# Schematic.net
KiCad netlist of a schematic drawn in EAGLE
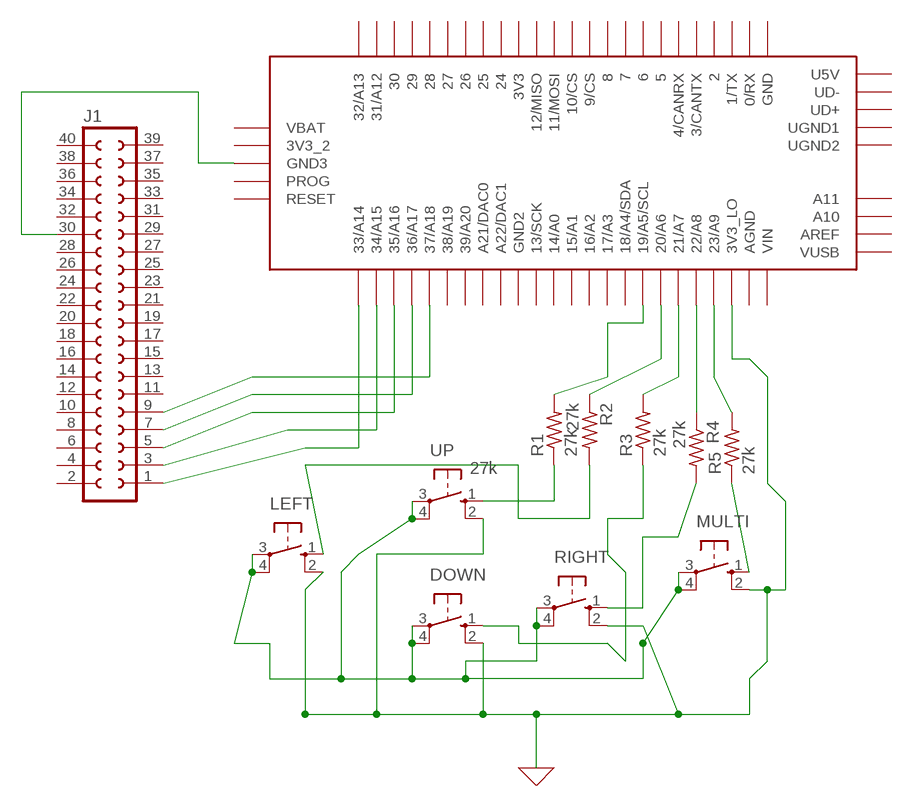
[diagram p0: schematic, sheet 1]

(export (version "E")
  (design (tool "Eeschema 10.0.6"))
  (components
    (comp (ref "DOWN")
      (value "27k")
      (footprint "eagle-import:B3F-10XX")
      (fields (field (name "MPN") "B3F-1000"))
      (libsource (lib "eagle-import") (part "10-XX"))
    )
    (comp (ref "J1")
      (value "SOCKET-40V")
      (footprint "eagle-import:S40V")
      (libsource (lib "eagle-import") (part "SOCKET-40V"))
    )
    (comp (ref "LEFT")
      (value "27k")
      (footprint "eagle-import:B3F-10XX")
      (fields (field (name "MPN") "B3F-1000"))
      (libsource (lib "eagle-import") (part "10-XX"))
    )
    (comp (ref "MULTI")
      (value "27k")
      (footprint "eagle-import:B3F-10XX")
      (fields (field (name "MPN") "B3F-1000"))
      (libsource (lib "eagle-import") (part "10-XX"))
    )
    (comp (ref "R1")
      (value "27k")
      (footprint "eagle-import:0204V")
      (libsource (lib "eagle-import") (part "R-US_0204/2V"))
    )
    (comp (ref "R2")
      (value "27k")
      (footprint "eagle-import:0204V")
      (libsource (lib "eagle-import") (part "R-US_0204/2V"))
    )
    (comp (ref "R3")
      (value "27k")
      (footprint "eagle-import:0204V")
      (libsource (lib "eagle-import") (part "R-US_0204/2V"))
    )
    (comp (ref "R4")
      (value "27k")
      (footprint "eagle-import:0204V")
      (libsource (lib "eagle-import") (part "R-US_0204/2V"))
    )
    (comp (ref "R5")
      (value "27k")
      (footprint "eagle-import:0204V")
      (libsource (lib "eagle-import") (part "R-US_0204/2V"))
    )
    (comp (ref "RIGHT")
      (value "27k")
      (footprint "eagle-import:B3F-10XX")
      (fields (field (name "MPN") "B3F-1000"))
      (libsource (lib "eagle-import") (part "10-XX"))
    )
    (comp (ref "U$2")
      (value "TEENSY_3.5/3.6")
      (footprint "eagle-import:TEENSY_3.5_3.6")
      (libsource (lib "eagle-import") (part "TEENSY_3.5/3.6"))
    )
    (comp (ref "UP")
      (value "27k")
      (footprint "eagle-import:B3F-10XX")
      (fields (field (name "MPN") "B3F-1000"))
      (libsource (lib "eagle-import") (part "10-XX"))
    )
  )
  (nets
    (net (code "1") (name "GND") (class "Default")
      (node (ref "DOWN") (pin "2") (pinfunction "S1_2") (pintype "passive"))
      (node (ref "DOWN") (pin "3") (pinfunction "P_3") (pintype "passive"))
      (node (ref "DOWN") (pin "4") (pinfunction "P1_4") (pintype "passive"))
      (node (ref "LEFT") (pin "2") (pinfunction "S1_2") (pintype "passive"))
      (node (ref "LEFT") (pin "3") (pinfunction "P_3") (pintype "passive"))
      (node (ref "LEFT") (pin "4") (pinfunction "P1_4") (pintype "passive"))
      (node (ref "MULTI") (pin "2") (pinfunction "S1_2") (pintype "passive"))
      (node (ref "MULTI") (pin "3") (pinfunction "P_3") (pintype "passive"))
      (node (ref "MULTI") (pin "4") (pinfunction "P1_4") (pintype "passive"))
      (node (ref "RIGHT") (pin "2") (pinfunction "S1_2") (pintype "passive"))
      (node (ref "RIGHT") (pin "3") (pinfunction "P_3") (pintype "passive"))
      (node (ref "RIGHT") (pin "4") (pinfunction "P1_4") (pintype "passive"))
      (node (ref "U$2") (pin "3V3_LO") (pinfunction "3V3_LO_3V3_LO") (pintype "bidirectional"))
      (node (ref "UP") (pin "2") (pinfunction "S1_2") (pintype "passive"))
      (node (ref "UP") (pin "3") (pinfunction "P_3") (pintype "passive"))
      (node (ref "UP") (pin "4") (pinfunction "P1_4") (pintype "passive"))
    )
    (net (code "2") (name "Net-(DOWN-S)") (class "Default")
      (node (ref "DOWN") (pin "1") (pinfunction "S_1") (pintype "passive"))
      (node (ref "R3") (pin "1") (pinfunction "1_1") (pintype "passive"))
    )
    (net (code "3") (name "Net-(J1-Pad1)") (class "Default")
      (node (ref "J1") (pin "1") (pinfunction "1_1") (pintype "passive"))
      (node (ref "U$2") (pin "33/A14") (pinfunction "33/A14_33/A14") (pintype "bidirectional"))
    )
    (net (code "4") (name "Net-(J1-Pad3)") (class "Default")
      (node (ref "J1") (pin "3") (pinfunction "3_3") (pintype "passive"))
      (node (ref "U$2") (pin "34/A15") (pinfunction "34/A15_34/A15") (pintype "bidirectional"))
    )
    (net (code "5") (name "Net-(J1-Pad5)") (class "Default")
      (node (ref "J1") (pin "5") (pinfunction "5_5") (pintype "passive"))
      (node (ref "U$2") (pin "35/A16") (pinfunction "35/A16_35/A16") (pintype "bidirectional"))
    )
    (net (code "6") (name "Net-(J1-Pad7)") (class "Default")
      (node (ref "J1") (pin "7") (pinfunction "7_7") (pintype "passive"))
      (node (ref "U$2") (pin "36/A17") (pinfunction "36/A17_36/A17") (pintype "bidirectional"))
    )
    (net (code "7") (name "Net-(J1-Pad9)") (class "Default")
      (node (ref "J1") (pin "9") (pinfunction "9_9") (pintype "passive"))
      (node (ref "U$2") (pin "37/A18") (pinfunction "37/A18_37/A18") (pintype "bidirectional"))
    )
    (net (code "8") (name "Net-(J1-Pad30)") (class "Default")
      (node (ref "J1") (pin "30") (pinfunction "30_30") (pintype "passive"))
      (node (ref "U$2") (pin "GND3") (pinfunction "GND3_GND3") (pintype "bidirectional"))
    )
    (net (code "9") (name "Net-(LEFT-S)") (class "Default")
      (node (ref "LEFT") (pin "1") (pinfunction "S_1") (pintype "passive"))
      (node (ref "R2") (pin "2") (pinfunction "2_2") (pintype "passive"))
    )
    (net (code "10") (name "Net-(MULTI-S)") (class "Default")
      (node (ref "MULTI") (pin "1") (pinfunction "S_1") (pintype "passive"))
      (node (ref "R5") (pin "1") (pinfunction "1_1") (pintype "passive"))
    )
    (net (code "11") (name "Net-(R1-Pad2)") (class "Default")
      (node (ref "R1") (pin "2") (pinfunction "2_2") (pintype "passive"))
      (node (ref "U$2") (pin "19/A5/SCL") (pinfunction "19/A5/SCL_19/A5/SCL") (pintype "bidirectional"))
    )
    (net (code "12") (name "Net-(R2-Pad1)") (class "Default")
      (node (ref "R2") (pin "1") (pinfunction "1_1") (pintype "passive"))
      (node (ref "U$2") (pin "20/A6") (pinfunction "20/A6_20/A6") (pintype "bidirectional"))
    )
    (net (code "13") (name "Net-(R3-Pad2)") (class "Default")
      (node (ref "R3") (pin "2") (pinfunction "2_2") (pintype "passive"))
      (node (ref "U$2") (pin "21/A7") (pinfunction "21/A7_21/A7") (pintype "bidirectional"))
    )
    (net (code "14") (name "Net-(R4-Pad1)") (class "Default")
      (node (ref "R4") (pin "1") (pinfunction "1_1") (pintype "passive"))
      (node (ref "U$2") (pin "22/A8") (pinfunction "22/A8_22/A8") (pintype "bidirectional"))
    )
    (net (code "15") (name "Net-(R5-Pad2)") (class "Default")
      (node (ref "R5") (pin "2") (pinfunction "2_2") (pintype "passive"))
      (node (ref "U$2") (pin "23/A9") (pinfunction "23/A9_23/A9") (pintype "bidirectional"))
    )
    (net (code "16") (name "Net-(RIGHT-S)") (class "Default")
      (node (ref "R4") (pin "2") (pinfunction "2_2") (pintype "passive"))
      (node (ref "RIGHT") (pin "1") (pinfunction "S_1") (pintype "passive"))
    )
    (net (code "17") (name "Net-(UP-S)") (class "Default")
      (node (ref "R1") (pin "1") (pinfunction "1_1") (pintype "passive"))
      (node (ref "UP") (pin "1") (pinfunction "S_1") (pintype "passive"))
    )
    (net (code "18") (name "unconnected-(J1-Pad2)") (class "Default")
      (node (ref "J1") (pin "2") (pinfunction "2_2") (pintype "passive"))
    )
    (net (code "19") (name "unconnected-(J1-Pad4)") (class "Default")
      (node (ref "J1") (pin "4") (pinfunction "4_4") (pintype "passive"))
    )
    (net (code "20") (name "unconnected-(J1-Pad6)") (class "Default")
      (node (ref "J1") (pin "6") (pinfunction "6_6") (pintype "passive"))
    )
    (net (code "21") (name "unconnected-(J1-Pad8)") (class "Default")
      (node (ref "J1") (pin "8") (pinfunction "8_8") (pintype "passive"))
    )
    (net (code "22") (name "unconnected-(J1-Pad10)") (class "Default")
      (node (ref "J1") (pin "10") (pinfunction "10_10") (pintype "passive"))
    )
    (net (code "23") (name "unconnected-(J1-Pad11)") (class "Default")
      (node (ref "J1") (pin "11") (pinfunction "11_11") (pintype "passive"))
    )
    (net (code "24") (name "unconnected-(J1-Pad12)") (class "Default")
      (node (ref "J1") (pin "12") (pinfunction "12_12") (pintype "passive"))
    )
    (net (code "25") (name "unconnected-(J1-Pad13)") (class "Default")
      (node (ref "J1") (pin "13") (pinfunction "13_13") (pintype "passive"))
    )
    (net (code "26") (name "unconnected-(J1-Pad14)") (class "Default")
      (node (ref "J1") (pin "14") (pinfunction "14_14") (pintype "passive"))
    )
    (net (code "27") (name "unconnected-(J1-Pad15)") (class "Default")
      (node (ref "J1") (pin "15") (pinfunction "15_15") (pintype "passive"))
    )
    (net (code "28") (name "unconnected-(J1-Pad16)") (class "Default")
      (node (ref "J1") (pin "16") (pinfunction "16_16") (pintype "passive"))
    )
    (net (code "29") (name "unconnected-(J1-Pad17)") (class "Default")
      (node (ref "J1") (pin "17") (pinfunction "17_17") (pintype "passive"))
    )
    (net (code "30") (name "unconnected-(J1-Pad18)") (class "Default")
      (node (ref "J1") (pin "18") (pinfunction "18_18") (pintype "passive"))
    )
    (net (code "31") (name "unconnected-(J1-Pad19)") (class "Default")
      (node (ref "J1") (pin "19") (pinfunction "19_19") (pintype "passive"))
    )
    (net (code "32") (name "unconnected-(J1-Pad20)") (class "Default")
      (node (ref "J1") (pin "20") (pinfunction "20_20") (pintype "passive"))
    )
    (net (code "33") (name "unconnected-(J1-Pad21)") (class "Default")
      (node (ref "J1") (pin "21") (pinfunction "21_21") (pintype "passive"))
    )
    (net (code "34") (name "unconnected-(J1-Pad22)") (class "Default")
      (node (ref "J1") (pin "22") (pinfunction "22_22") (pintype "passive"))
    )
    (net (code "35") (name "unconnected-(J1-Pad23)") (class "Default")
      (node (ref "J1") (pin "23") (pinfunction "23_23") (pintype "passive"))
    )
    (net (code "36") (name "unconnected-(J1-Pad24)") (class "Default")
      (node (ref "J1") (pin "24") (pinfunction "24_24") (pintype "passive"))
    )
    (net (code "37") (name "unconnected-(J1-Pad25)") (class "Default")
      (node (ref "J1") (pin "25") (pinfunction "25_25") (pintype "passive"))
    )
    (net (code "38") (name "unconnected-(J1-Pad26)") (class "Default")
      (node (ref "J1") (pin "26") (pinfunction "26_26") (pintype "passive"))
    )
    (net (code "39") (name "unconnected-(J1-Pad27)") (class "Default")
      (node (ref "J1") (pin "27") (pinfunction "27_27") (pintype "passive"))
    )
    (net (code "40") (name "unconnected-(J1-Pad28)") (class "Default")
      (node (ref "J1") (pin "28") (pinfunction "28_28") (pintype "passive"))
    )
    (net (code "41") (name "unconnected-(J1-Pad29)") (class "Default")
      (node (ref "J1") (pin "29") (pinfunction "29_29") (pintype "passive"))
    )
    (net (code "42") (name "unconnected-(J1-Pad31)") (class "Default")
      (node (ref "J1") (pin "31") (pinfunction "31_31") (pintype "passive"))
    )
    (net (code "43") (name "unconnected-(J1-Pad32)") (class "Default")
      (node (ref "J1") (pin "32") (pinfunction "32_32") (pintype "passive"))
    )
    (net (code "44") (name "unconnected-(J1-Pad33)") (class "Default")
      (node (ref "J1") (pin "33") (pinfunction "33_33") (pintype "passive"))
    )
    (net (code "45") (name "unconnected-(J1-Pad34)") (class "Default")
      (node (ref "J1") (pin "34") (pinfunction "34_34") (pintype "passive"))
    )
    (net (code "46") (name "unconnected-(J1-Pad35)") (class "Default")
      (node (ref "J1") (pin "35") (pinfunction "35_35") (pintype "passive"))
    )
    (net (code "47") (name "unconnected-(J1-Pad36)") (class "Default")
      (node (ref "J1") (pin "36") (pinfunction "36_36") (pintype "passive"))
    )
    (net (code "48") (name "unconnected-(J1-Pad37)") (class "Default")
      (node (ref "J1") (pin "37") (pinfunction "37_37") (pintype "passive"))
    )
    (net (code "49") (name "unconnected-(J1-Pad38)") (class "Default")
      (node (ref "J1") (pin "38") (pinfunction "38_38") (pintype "passive"))
    )
    (net (code "50") (name "unconnected-(J1-Pad39)") (class "Default")
      (node (ref "J1") (pin "39") (pinfunction "39_39") (pintype "passive"))
    )
    (net (code "51") (name "unconnected-(J1-Pad40)") (class "Default")
      (node (ref "J1") (pin "40") (pinfunction "40_40") (pintype "passive"))
    )
    (net (code "52") (name "unconnected-(U$2-A21{slash}DAC0-Pad21{slash}DAC0)") (class "Default")
      (node (ref "U$2") (pin "21/DAC0") (pinfunction "A21/DAC0_21/DAC0") (pintype "bidirectional"))
    )
    (net (code "53") (name "unconnected-(U$2-Pad0{slash}RX)") (class "Default")
      (node (ref "U$2") (pin "0/RX") (pinfunction "0/RX_0/RX") (pintype "bidirectional"))
    )
    (net (code "54") (name "unconnected-(U$2-Pad1{slash}TX)") (class "Default")
      (node (ref "U$2") (pin "1/TX") (pinfunction "1/TX_1/TX") (pintype "bidirectional"))
    )
    (net (code "55") (name "unconnected-(U$2-Pad2)") (class "Default")
      (node (ref "U$2") (pin "2") (pinfunction "2_2") (pintype "bidirectional"))
    )
    (net (code "56") (name "unconnected-(U$2-Pad3V3)") (class "Default")
      (node (ref "U$2") (pin "3V3") (pinfunction "3V3_3V3") (pintype "bidirectional"))
    )
    (net (code "57") (name "unconnected-(U$2-Pad3V3_2)") (class "Default")
      (node (ref "U$2") (pin "3V3_2") (pinfunction "3V3_2_3V3_2") (pintype "bidirectional"))
    )
    (net (code "58") (name "unconnected-(U$2-Pad3{slash}CANTX)") (class "Default")
      (node (ref "U$2") (pin "3/CANTX") (pinfunction "3/CANTX_3/CANTX") (pintype "bidirectional"))
    )
    (net (code "59") (name "unconnected-(U$2-Pad4{slash}CANRX)") (class "Default")
      (node (ref "U$2") (pin "4/CANRX") (pinfunction "4/CANRX_4/CANRX") (pintype "bidirectional"))
    )
    (net (code "60") (name "unconnected-(U$2-Pad5)") (class "Default")
      (node (ref "U$2") (pin "5") (pinfunction "5_5") (pintype "bidirectional"))
    )
    (net (code "61") (name "unconnected-(U$2-Pad6)") (class "Default")
      (node (ref "U$2") (pin "6") (pinfunction "6_6") (pintype "bidirectional"))
    )
    (net (code "62") (name "unconnected-(U$2-Pad7)") (class "Default")
      (node (ref "U$2") (pin "7") (pinfunction "7_7") (pintype "bidirectional"))
    )
    (net (code "63") (name "unconnected-(U$2-Pad8)") (class "Default")
      (node (ref "U$2") (pin "8") (pinfunction "8_8") (pintype "bidirectional"))
    )
    (net (code "64") (name "unconnected-(U$2-Pad9{slash}CS)") (class "Default")
      (node (ref "U$2") (pin "9/CS") (pinfunction "9/CS_9/CS") (pintype "bidirectional"))
    )
    (net (code "65") (name "unconnected-(U$2-Pad10{slash}CS)") (class "Default")
      (node (ref "U$2") (pin "10/CS") (pinfunction "10/CS_10/CS") (pintype "bidirectional"))
    )
    (net (code "66") (name "unconnected-(U$2-Pad11{slash}MOSI)") (class "Default")
      (node (ref "U$2") (pin "11/MOSI") (pinfunction "11/MOSI_11/MOSI") (pintype "bidirectional"))
    )
    (net (code "67") (name "unconnected-(U$2-Pad12{slash}MISO)") (class "Default")
      (node (ref "U$2") (pin "12/MISO") (pinfunction "12/MISO_12/MISO") (pintype "bidirectional"))
    )
    (net (code "68") (name "unconnected-(U$2-Pad13{slash}SCK)") (class "Default")
      (node (ref "U$2") (pin "13/SCK") (pinfunction "13/SCK_13/SCK") (pintype "bidirectional"))
    )
    (net (code "69") (name "unconnected-(U$2-Pad14{slash}A0)") (class "Default")
      (node (ref "U$2") (pin "14/A0") (pinfunction "14/A0_14/A0") (pintype "bidirectional"))
    )
    (net (code "70") (name "unconnected-(U$2-Pad15{slash}A1)") (class "Default")
      (node (ref "U$2") (pin "15/A1") (pinfunction "15/A1_15/A1") (pintype "bidirectional"))
    )
    (net (code "71") (name "unconnected-(U$2-Pad16{slash}A2)") (class "Default")
      (node (ref "U$2") (pin "16/A2") (pinfunction "16/A2_16/A2") (pintype "bidirectional"))
    )
    (net (code "72") (name "unconnected-(U$2-Pad17{slash}A3)") (class "Default")
      (node (ref "U$2") (pin "17/A3") (pinfunction "17/A3_17/A3") (pintype "bidirectional"))
    )
    (net (code "73") (name "unconnected-(U$2-Pad18{slash}A4{slash}SDA)") (class "Default")
      (node (ref "U$2") (pin "18/A4/SDA") (pinfunction "18/A4/SDA_18/A4/SDA") (pintype "bidirectional"))
    )
    (net (code "74") (name "unconnected-(U$2-Pad24)") (class "Default")
      (node (ref "U$2") (pin "24") (pinfunction "24_24") (pintype "bidirectional"))
    )
    (net (code "75") (name "unconnected-(U$2-Pad25)") (class "Default")
      (node (ref "U$2") (pin "25") (pinfunction "25_25") (pintype "bidirectional"))
    )
    (net (code "76") (name "unconnected-(U$2-Pad26)") (class "Default")
      (node (ref "U$2") (pin "26") (pinfunction "26_26") (pintype "bidirectional"))
    )
    (net (code "77") (name "unconnected-(U$2-Pad27)") (class "Default")
      (node (ref "U$2") (pin "27") (pinfunction "27_27") (pintype "bidirectional"))
    )
    (net (code "78") (name "unconnected-(U$2-Pad28)") (class "Default")
      (node (ref "U$2") (pin "28") (pinfunction "28_28") (pintype "bidirectional"))
    )
    (net (code "79") (name "unconnected-(U$2-Pad29)") (class "Default")
      (node (ref "U$2") (pin "29") (pinfunction "29_29") (pintype "bidirectional"))
    )
    (net (code "80") (name "unconnected-(U$2-Pad30)") (class "Default")
      (node (ref "U$2") (pin "30") (pinfunction "30_30") (pintype "bidirectional"))
    )
    (net (code "81") (name "unconnected-(U$2-Pad31{slash}A12)") (class "Default")
      (node (ref "U$2") (pin "31/A12") (pinfunction "31/A12_31/A12") (pintype "bidirectional"))
    )
    (net (code "82") (name "unconnected-(U$2-Pad32{slash}A13)") (class "Default")
      (node (ref "U$2") (pin "32/A13") (pinfunction "32/A13_32/A13") (pintype "bidirectional"))
    )
    (net (code "83") (name "unconnected-(U$2-Pad38{slash}A19)") (class "Default")
      (node (ref "U$2") (pin "38/A19") (pinfunction "38/A19_38/A19") (pintype "bidirectional"))
    )
    (net (code "84") (name "unconnected-(U$2-Pad39{slash}A20)") (class "Default")
      (node (ref "U$2") (pin "39/A20") (pinfunction "39/A20_39/A20") (pintype "bidirectional"))
    )
    (net (code "85") (name "unconnected-(U$2-PadA10)") (class "Default")
      (node (ref "U$2") (pin "A10") (pinfunction "A10_A10") (pintype "bidirectional"))
    )
    (net (code "86") (name "unconnected-(U$2-PadA11)") (class "Default")
      (node (ref "U$2") (pin "A11") (pinfunction "A11_A11") (pintype "bidirectional"))
    )
    (net (code "87") (name "unconnected-(U$2-PadA22{slash}DAC1)") (class "Default")
      (node (ref "U$2") (pin "A22/DAC1") (pinfunction "A22/DAC1_A22/DAC1") (pintype "bidirectional"))
    )
    (net (code "88") (name "unconnected-(U$2-PadAGND)") (class "Default")
      (node (ref "U$2") (pin "AGND") (pinfunction "AGND_AGND") (pintype "bidirectional"))
    )
    (net (code "89") (name "unconnected-(U$2-PadAREF)") (class "Default")
      (node (ref "U$2") (pin "AREF") (pinfunction "AREF_AREF") (pintype "bidirectional"))
    )
    (net (code "90") (name "unconnected-(U$2-PadGND)") (class "Default")
      (node (ref "U$2") (pin "GND") (pinfunction "GND_GND") (pintype "bidirectional"))
    )
    (net (code "91") (name "unconnected-(U$2-PadGND2)") (class "Default")
      (node (ref "U$2") (pin "GND2") (pinfunction "GND2_GND2") (pintype "bidirectional"))
    )
    (net (code "92") (name "unconnected-(U$2-PadPROG)") (class "Default")
      (node (ref "U$2") (pin "PROG") (pinfunction "PROG_PROG") (pintype "bidirectional"))
    )
    (net (code "93") (name "unconnected-(U$2-PadRESET)") (class "Default")
      (node (ref "U$2") (pin "RESET") (pinfunction "RESET_RESET") (pintype "bidirectional"))
    )
    (net (code "94") (name "unconnected-(U$2-PadU5V)") (class "Default")
      (node (ref "U$2") (pin "U5V") (pinfunction "U5V_U5V") (pintype "bidirectional"))
    )
    (net (code "95") (name "unconnected-(U$2-PadUD+)") (class "Default")
      (node (ref "U$2") (pin "UD+") (pinfunction "UD+_UD+") (pintype "bidirectional"))
    )
    (net (code "96") (name "unconnected-(U$2-PadUD-)") (class "Default")
      (node (ref "U$2") (pin "UD-") (pinfunction "UD-_UD-") (pintype "bidirectional"))
    )
    (net (code "97") (name "unconnected-(U$2-PadUGND1)") (class "Default")
      (node (ref "U$2") (pin "UGND1") (pinfunction "UGND1_UGND1") (pintype "bidirectional"))
    )
    (net (code "98") (name "unconnected-(U$2-PadUGND2)") (class "Default")
      (node (ref "U$2") (pin "UGND2") (pinfunction "UGND2_UGND2") (pintype "bidirectional"))
    )
    (net (code "99") (name "unconnected-(U$2-PadVBAT)") (class "Default")
      (node (ref "U$2") (pin "VBAT") (pinfunction "VBAT_VBAT") (pintype "bidirectional"))
    )
    (net (code "100") (name "unconnected-(U$2-PadVIN)") (class "Default")
      (node (ref "U$2") (pin "VIN") (pinfunction "VIN_VIN") (pintype "bidirectional"))
    )
    (net (code "101") (name "unconnected-(U$2-PadVUSB)") (class "Default")
      (node (ref "U$2") (pin "VUSB") (pinfunction "VUSB_VUSB") (pintype "bidirectional"))
    )
  )
)
